# Step_Moter_Control.net
KiCad netlist of a schematic drawn in Altium Designer
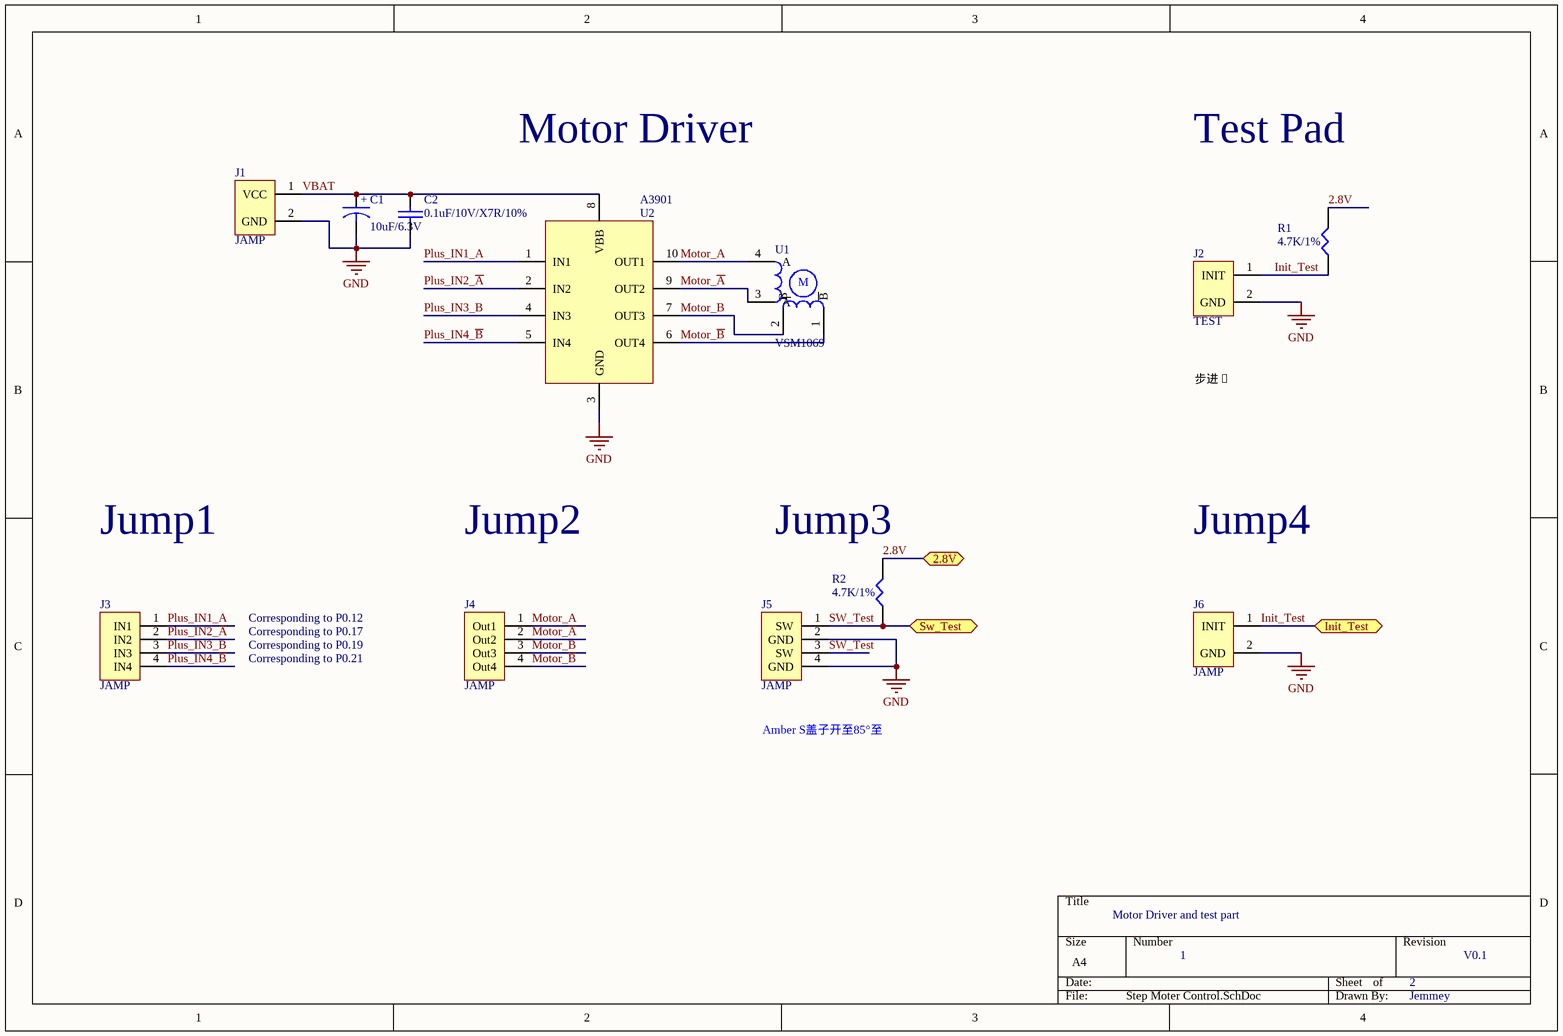
[diagram p0: Step Moter Control.SchDoc]

(export (version "E")
  (design (tool "Eeschema 10.0.6"))
  (components
    (comp (ref "C1")
      (value "10uF/6.3V")
      (footprint "3216")
      (description "厂家：ROHM，型号：")
      (libsource (lib "MoJi LIB") (part "Capacitor"))
    )
    (comp (ref "C2")
      (value "0.1uF/10V/X7R/10%")
      (footprint "0402C")
      (description "厂家：Murata，型号：GRM155R71A104KA01D")
      (libsource (lib "*") (part "CAP"))
    )
    (comp (ref "J1")
      (value "JAMP")
      (footprint "Debug- 1.27*2")
      (description "厂家：暂定，型号：暂定")
      (libsource (lib "Step Moter Control") (part "JAMP"))
    )
    (comp (ref "J2")
      (value "TEST")
      (footprint "Debug- 1.27*2")
      (description "厂家：暂定，型号：暂定")
      (libsource (lib "Step Moter Control") (part "TEST"))
    )
    (comp (ref "J3")
      (value "JAMP")
      (footprint "Debug- 1.27*4")
      (description "厂家：暂定，型号：暂定")
      (libsource (lib "") (part "JAMP_1"))
    )
    (comp (ref "J4")
      (value "JAMP")
      (footprint "Debug- 1.27*4")
      (description "厂家：暂定，型号：暂定")
      (libsource (lib "") (part "JAMP_2"))
    )
    (comp (ref "J5")
      (value "JAMP")
      (footprint "Debug- 1.27*4")
      (description "厂家：暂定，型号：暂定")
      (libsource (lib "") (part "JAMP_3"))
    )
    (comp (ref "J6")
      (value "JAMP")
      (footprint "Debug- 1.27*2")
      (description "厂家：暂定，型号：暂定")
      (libsource (lib "Step Moter Control") (part "JAMP"))
    )
    (comp (ref "R1")
      (value "4.7K/1%")
      (footprint "0402R")
      (description "厂家：Yageo，型号：RC0402FR-074K7L")
      (libsource (lib "*") (part "RES1"))
    )
    (comp (ref "R2")
      (value "4.7K/1%")
      (footprint "0402R")
      (description "厂家：Yageo，型号：RC0402FR-074K7L")
      (libsource (lib "*") (part "RES1"))
    )
    (comp (ref "U1")
      (value "VSM1069")
      (footprint "FPC_CON5-6200")
      (description "厂家：常州唯可泰，型号：VSM1069；二相步进电机")
      (libsource (lib "Step Moter Control_1") (part "VSM1069"))
    )
    (comp (ref "U2")
      (value "A3901")
      (footprint "DFN10")
      (description "厂家：Allegro ，型号：A3901 Two phase stepper motor drives")
      (libsource (lib "Schlib1") (part "A3901"))
    )
  )
  (nets
    (net (code "1") (name "/2.8V") (class "Default")
      (node (ref "R1") (pin "2") (pinfunction "2_2") (pintype "passive"))
      (node (ref "R2") (pin "2") (pinfunction "2_2") (pintype "passive"))
    )
    (net (code "2") (name "/Init_Test") (class "Default")
      (node (ref "J2") (pin "1") (pinfunction "INIT_1") (pintype "passive"))
      (node (ref "J6") (pin "1") (pinfunction "VCC_1") (pintype "passive"))
      (node (ref "R1") (pin "1") (pinfunction "1_1") (pintype "passive"))
    )
    (net (code "3") (name "/Motor_A") (class "Default")
      (node (ref "J4") (pin "1") (pinfunction "Out1_1") (pintype "passive"))
      (node (ref "U1") (pin "4") (pinfunction "A_4") (pintype "passive"))
      (node (ref "U2") (pin "10") (pinfunction "OUT1_10") (pintype "passive"))
    )
    (net (code "4") (name "/Motor_B") (class "Default")
      (node (ref "J4") (pin "3") (pinfunction "Out3_3") (pintype "passive"))
      (node (ref "U1") (pin "2") (pinfunction "B_2") (pintype "passive"))
      (node (ref "U2") (pin "7") (pinfunction "OUT3_7") (pintype "passive"))
    )
    (net (code "5") (name "/Motor_~{A}") (class "Default")
      (node (ref "J4") (pin "2") (pinfunction "Out2_2") (pintype "passive"))
      (node (ref "U1") (pin "3") (pinfunction "~{A}_3") (pintype "passive"))
      (node (ref "U2") (pin "9") (pinfunction "OUT2_9") (pintype "passive"))
    )
    (net (code "6") (name "/Motor_~{B}") (class "Default")
      (node (ref "J4") (pin "4") (pinfunction "Out4_4") (pintype "passive"))
      (node (ref "U1") (pin "1") (pinfunction "~{B}_1") (pintype "passive"))
      (node (ref "U2") (pin "6") (pinfunction "OUT4_6") (pintype "passive"))
    )
    (net (code "7") (name "/Plus_IN1_A") (class "Default")
      (node (ref "J3") (pin "1") (pinfunction "IN1_1") (pintype "passive"))
      (node (ref "U2") (pin "1") (pinfunction "IN1_1") (pintype "passive"))
    )
    (net (code "8") (name "/Plus_IN2_~{A}") (class "Default")
      (node (ref "J3") (pin "2") (pinfunction "IN2_2") (pintype "passive"))
      (node (ref "U2") (pin "2") (pinfunction "IN2_2") (pintype "passive"))
    )
    (net (code "9") (name "/Plus_IN3_B") (class "Default")
      (node (ref "J3") (pin "3") (pinfunction "IN3_3") (pintype "passive"))
      (node (ref "U2") (pin "4") (pinfunction "IN3_4") (pintype "passive"))
    )
    (net (code "10") (name "/Plus_IN4_~{B}") (class "Default")
      (node (ref "J3") (pin "4") (pinfunction "IN4_4") (pintype "passive"))
      (node (ref "U2") (pin "5") (pinfunction "IN4_5") (pintype "passive"))
    )
    (net (code "11") (name "/SW_Test") (class "Default")
      (node (ref "J5") (pin "1") (pinfunction "SW_1") (pintype "passive"))
      (node (ref "J5") (pin "3") (pinfunction "SW_3") (pintype "passive"))
      (node (ref "R2") (pin "1") (pinfunction "1_1") (pintype "passive"))
    )
    (net (code "12") (name "/VBAT") (class "Default")
      (node (ref "C1") (pin "1") (pinfunction "1_1") (pintype "passive"))
      (node (ref "C2") (pin "1") (pinfunction "1_1") (pintype "passive"))
      (node (ref "J1") (pin "1") (pinfunction "VCC_1") (pintype "passive"))
      (node (ref "U2") (pin "8") (pinfunction "VBB_8") (pintype "passive"))
    )
    (net (code "13") (name "GND") (class "Default")
      (node (ref "C1") (pin "2") (pinfunction "2_2") (pintype "passive"))
      (node (ref "C2") (pin "2") (pinfunction "2_2") (pintype "passive"))
      (node (ref "J1") (pin "2") (pinfunction "GND_2") (pintype "passive"))
      (node (ref "J2") (pin "2") (pinfunction "GND_2") (pintype "passive"))
      (node (ref "J5") (pin "2") (pinfunction "GND_2") (pintype "passive"))
      (node (ref "J5") (pin "4") (pinfunction "GND_4") (pintype "passive"))
      (node (ref "J6") (pin "2") (pinfunction "GND_2") (pintype "passive"))
      (node (ref "U2") (pin "3") (pinfunction "GND_3") (pintype "passive"))
    )
  )
)
